# Substractor.net
KiCad netlist of a schematic drawn in Altium Designer
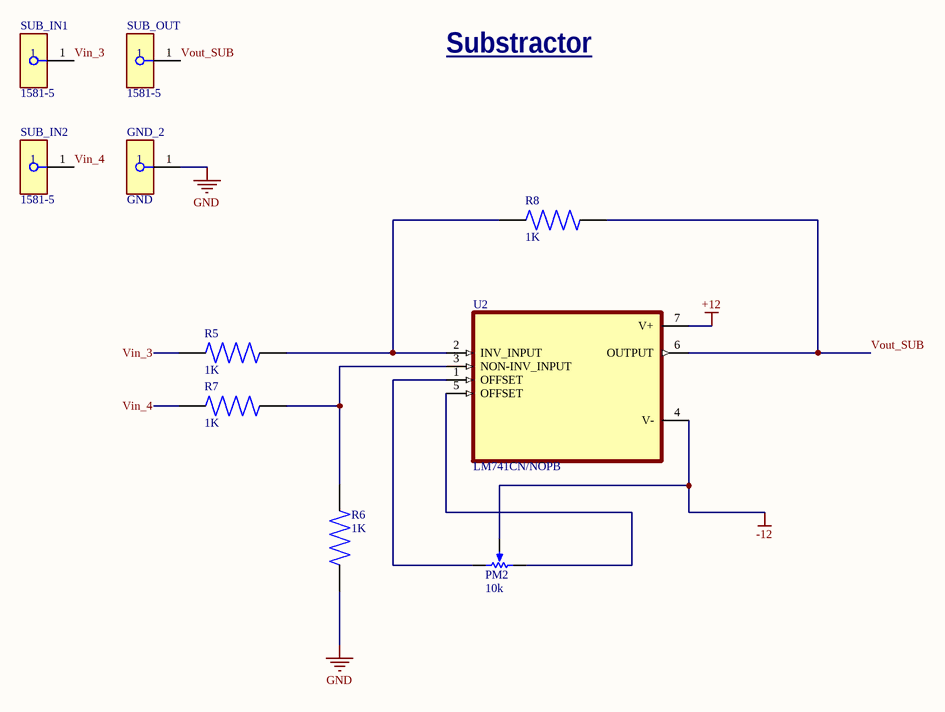
[diagram p0: Substractor.SchDoc]

(export (version "E")
  (design (tool "Eeschema 10.0.6"))
  (components
    (comp (ref "GND_2")
      (value "GND")
      (footprint "FP-1581-5-MFG")
      (description "CONN BANANA JACK TURRET GREEN")
      (libsource (lib "Altium Content Vault") (part "c5c826e0c4b67fe3b42ef77f2d4decc"))
    )
    (comp (ref "PM2")
      (value "10k")
      (footprint "BOUR-3362P")
      (description "Square Trimpot(R) Trimming Potentiometer, 10 KOhm, 300 V, -55 to 125 degC, 3-Pin THD, RoHS, Tube")
      (fields (field (name "TOLERANCE") "1%"))
      (libsource (lib "Altium Content Vault") (part "RES-POT-3"))
    )
    (comp (ref "R5")
      (value "1K")
      (footprint "RESAD1100W55L680D260")
      (description "1.07 kOhms Â±1% 0.25W, 1/4W Through Hole Resistor Axial - Metal Film")
      (fields (field (name "MF") "Yageo") (field (name "MP") "MFR-25FBF52-1K"))
      (libsource (lib "MFR-25FBF52-1K") (part "MFR-25FBF52-1K"))
    )
    (comp (ref "R6")
      (value "1K")
      (footprint "RESAD1100W55L680D260")
      (description "1.07 kOhms Â±1% 0.25W, 1/4W Through Hole Resistor Axial - Metal Film")
      (fields (field (name "MF") "Yageo") (field (name "MP") "MFR-25FBF52-1K"))
      (libsource (lib "MFR-25FBF52-1K") (part "MFR-25FBF52-1K"))
    )
    (comp (ref "R7")
      (value "1K")
      (footprint "RESAD1100W55L680D260")
      (description "1.07 kOhms Â±1% 0.25W, 1/4W Through Hole Resistor Axial - Metal Film")
      (fields (field (name "MF") "Yageo") (field (name "MP") "MFR-25FBF52-1K"))
      (libsource (lib "MFR-25FBF52-1K") (part "MFR-25FBF52-1K"))
    )
    (comp (ref "R8")
      (value "1K")
      (footprint "RESAD1100W55L680D260")
      (description "1.07 kOhms Â±1% 0.25W, 1/4W Through Hole Resistor Axial - Metal Film")
      (fields (field (name "MF") "Yageo") (field (name "MP") "MFR-25FBF52-1K"))
      (libsource (lib "MFR-25FBF52-1K") (part "MFR-25FBF52-1K"))
    )
    (comp (ref "SUB_IN1")
      (value "1581-5")
      (footprint "FP-1581-5-MFG")
      (description "CONN BANANA JACK TURRET GREEN")
      (libsource (lib "Altium Content Vault") (part "c5c826e0c4b67fe3b42ef77f2d4decc"))
    )
    (comp (ref "SUB_IN2")
      (value "1581-5")
      (footprint "FP-1581-5-MFG")
      (description "CONN BANANA JACK TURRET GREEN")
      (libsource (lib "Altium Content Vault") (part "c5c826e0c4b67fe3b42ef77f2d4decc"))
    )
    (comp (ref "SUB_OUT")
      (value "1581-5")
      (footprint "FP-1581-5-MFG")
      (description "CONN BANANA JACK TURRET GREEN")
      (libsource (lib "Altium Content Vault") (part "c5c826e0c4b67fe3b42ef77f2d4decc"))
    )
    (comp (ref "U2")
      (value "LM741CN/NOPB")
      (footprint "DIP794W45P254L959H508Q8")
      (description "Single, 44-V, 1-MHz operational amplifier")
      (fields (field (name "MF") "Texas Instruments"))
      (libsource (lib "LM741CN_NOPB (1)") (part "LM741CN/NOPB"))
    )
  )
  (nets
    (net (code "1") (name "+12") (class "Default")
      (node (ref "U2") (pin "7") (pinfunction "V+_7") (pintype "power_in"))
    )
    (net (code "2") (name "-12") (class "Default")
      (node (ref "PM2") (pin "2") (pinfunction "S_2") (pintype "passive"))
      (node (ref "U2") (pin "4") (pinfunction "V-_4") (pintype "power_in"))
    )
    (net (code "3") (name "/Vin_3") (class "Default")
      (node (ref "R5") (pin "1") (pinfunction "1_1") (pintype "passive"))
      (node (ref "SUB_IN1") (pin "1") (pinfunction "1_1") (pintype "passive"))
    )
    (net (code "4") (name "/Vin_4") (class "Default")
      (node (ref "R7") (pin "1") (pinfunction "1_1") (pintype "passive"))
      (node (ref "SUB_IN2") (pin "1") (pinfunction "1_1") (pintype "passive"))
    )
    (net (code "5") (name "/Vout_SUB") (class "Default")
      (node (ref "R8") (pin "2") (pinfunction "2_2") (pintype "passive"))
      (node (ref "SUB_OUT") (pin "1") (pinfunction "1_1") (pintype "passive"))
      (node (ref "U2") (pin "6") (pinfunction "OUTPUT_6") (pintype "output"))
    )
    (net (code "6") (name "GND") (class "Default")
      (node (ref "GND_2") (pin "1") (pinfunction "1_1") (pintype "passive"))
      (node (ref "R6") (pin "1") (pinfunction "1_1") (pintype "passive"))
    )
    (net (code "7") (name "Net-(PM2-CCW)") (class "Default")
      (node (ref "PM2") (pin "1") (pinfunction "CCW_1") (pintype "passive"))
      (node (ref "U2") (pin "5") (pinfunction "OFFSET_5") (pintype "input"))
    )
    (net (code "8") (name "Net-(PM2-CW)") (class "Default")
      (node (ref "PM2") (pin "3") (pinfunction "CW_3") (pintype "passive"))
      (node (ref "U2") (pin "1") (pinfunction "OFFSET_1") (pintype "input"))
    )
    (net (code "9") (name "Net-(U2-INV_INPUT)") (class "Default")
      (node (ref "R5") (pin "2") (pinfunction "2_2") (pintype "passive"))
      (node (ref "R8") (pin "1") (pinfunction "1_1") (pintype "passive"))
      (node (ref "U2") (pin "2") (pinfunction "INV_INPUT_2") (pintype "input"))
    )
    (net (code "10") (name "Net-(U2-NON-INV_INPUT)") (class "Default")
      (node (ref "R6") (pin "2") (pinfunction "2_2") (pintype "passive"))
      (node (ref "R7") (pin "2") (pinfunction "2_2") (pintype "passive"))
      (node (ref "U2") (pin "3") (pinfunction "NON-INV_INPUT_3") (pintype "input"))
    )
  )
)
